# zmFPGA.net
KiCad netlist of a schematic drawn in EAGLE
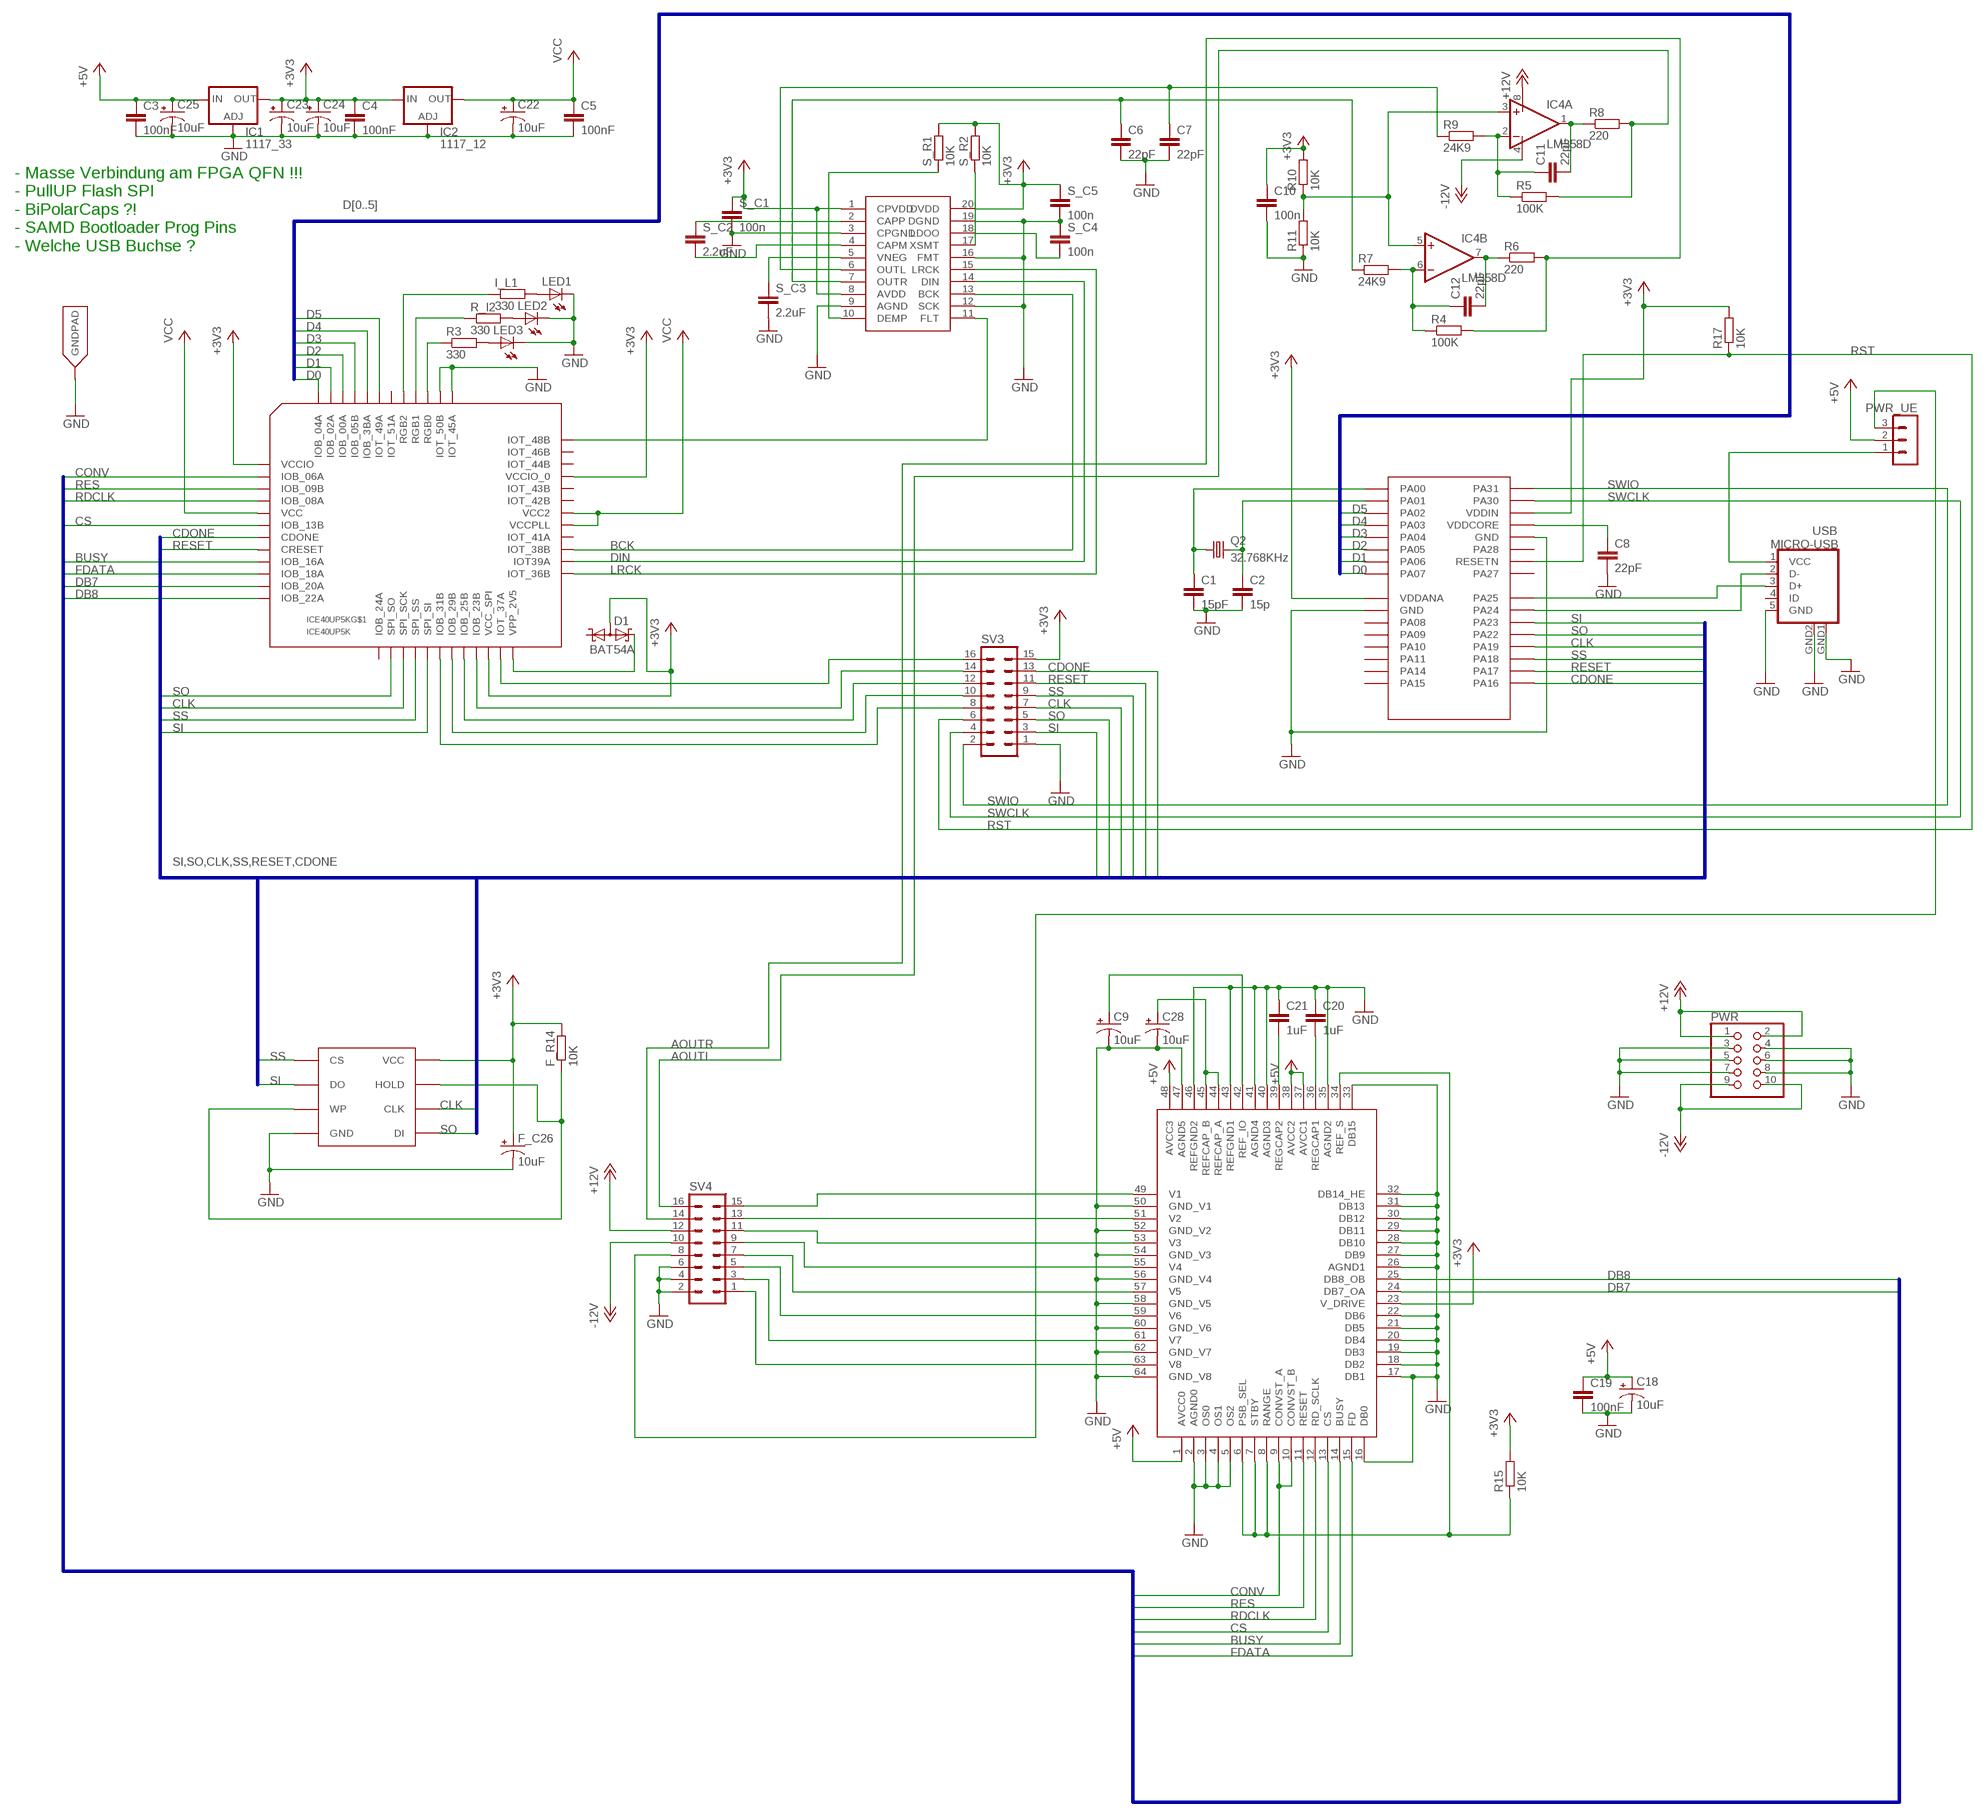
[diagram p0: schematic, sheet 1]

(export (version "E")
  (design (tool "Eeschema 10.0.6"))
  (components
    (comp (ref "AD7606")
      (value "AD7606")
      (footprint "eagle-import:LQFP64")
      (libsource (lib "eagle-import") (part "AD7606"))
    )
    (comp (ref "C1")
      (value "15pF")
      (footprint "eagle-import:C0805")
      (libsource (lib "eagle-import") (part "C-EUC0805"))
    )
    (comp (ref "C2")
      (value "15p")
      (footprint "eagle-import:C0805")
      (libsource (lib "eagle-import") (part "C-EUC0805"))
    )
    (comp (ref "C3")
      (value "100nF")
      (footprint "eagle-import:C0805")
      (libsource (lib "eagle-import") (part "C-EUC0805"))
    )
    (comp (ref "C4")
      (value "100nF")
      (footprint "eagle-import:C0805")
      (libsource (lib "eagle-import") (part "C-EUC0805"))
    )
    (comp (ref "C5")
      (value "100nF")
      (footprint "eagle-import:C0805")
      (libsource (lib "eagle-import") (part "C-EUC0805"))
    )
    (comp (ref "C6")
      (value "22pF")
      (footprint "eagle-import:C0805")
      (libsource (lib "eagle-import") (part "C-EUC0805"))
    )
    (comp (ref "C7")
      (value "22pF")
      (footprint "eagle-import:C0805")
      (libsource (lib "eagle-import") (part "C-EUC0805"))
    )
    (comp (ref "C8")
      (value "22pF")
      (footprint "eagle-import:C0805")
      (libsource (lib "eagle-import") (part "C-EUC0805"))
    )
    (comp (ref "C9")
      (value "10uF")
      (footprint "eagle-import:EIA3216")
      (libsource (lib "eagle-import") (part "10UF-POLAR-EIA3216-16V-10%(TANT)"))
    )
    (comp (ref "C10")
      (value "100n")
      (footprint "eagle-import:C0805")
      (libsource (lib "eagle-import") (part "C-EUC0805"))
    )
    (comp (ref "C11")
      (value "22pF")
      (footprint "eagle-import:C0805")
      (libsource (lib "eagle-import") (part "C-EUC0805"))
    )
    (comp (ref "C12")
      (value "22pF")
      (footprint "eagle-import:C0805")
      (libsource (lib "eagle-import") (part "C-EUC0805"))
    )
    (comp (ref "C18")
      (value "10uF")
      (footprint "eagle-import:EIA3216")
      (libsource (lib "eagle-import") (part "10UF-POLAR-EIA3216-16V-10%(TANT)"))
    )
    (comp (ref "C19")
      (value "100nF")
      (footprint "eagle-import:C0805")
      (libsource (lib "eagle-import") (part "C-EUC0805"))
    )
    (comp (ref "C20")
      (value "1uF")
      (footprint "eagle-import:C0805")
      (libsource (lib "eagle-import") (part "C-EUC0805"))
    )
    (comp (ref "C21")
      (value "1uF")
      (footprint "eagle-import:C0805")
      (libsource (lib "eagle-import") (part "C-EUC0805"))
    )
    (comp (ref "C22")
      (value "10uF")
      (footprint "eagle-import:EIA3216")
      (libsource (lib "eagle-import") (part "10UF-POLAR-EIA3216-16V-10%(TANT)"))
    )
    (comp (ref "C23")
      (value "10uF")
      (footprint "eagle-import:EIA3216")
      (libsource (lib "eagle-import") (part "10UF-POLAR-EIA3216-16V-10%(TANT)"))
    )
    (comp (ref "C24")
      (value "10uF")
      (footprint "eagle-import:EIA3216")
      (libsource (lib "eagle-import") (part "10UF-POLAR-EIA3216-16V-10%(TANT)"))
    )
    (comp (ref "C25")
      (value "10uF")
      (footprint "eagle-import:EIA3216")
      (libsource (lib "eagle-import") (part "10UF-POLAR-EIA3216-16V-10%(TANT)"))
    )
    (comp (ref "C28")
      (value "10uF")
      (footprint "eagle-import:EIA3216")
      (libsource (lib "eagle-import") (part "10UF-POLAR-EIA3216-16V-10%(TANT)"))
    )
    (comp (ref "D1")
      (value "BAT54A")
      (footprint "eagle-import:SOT23")
      (libsource (lib "eagle-import") (part "BAT54A"))
    )
    (comp (ref "F_C26")
      (value "10uF")
      (footprint "eagle-import:EIA3216")
      (libsource (lib "eagle-import") (part "10UF-POLAR-EIA3216-16V-10%(TANT)"))
    )
    (comp (ref "F_R14")
      (value "10K")
      (footprint "eagle-import:R0805")
      (libsource (lib "eagle-import") (part "R-EU_R0805"))
    )
    (comp (ref "IC1")
      (value "1117_33")
      (footprint "eagle-import:SOT223")
      (libsource (lib "eagle-import") (part "LD117A?S33TR"))
    )
    (comp (ref "IC2")
      (value "1117_12")
      (footprint "eagle-import:SOT223")
      (libsource (lib "eagle-import") (part "LD117A?S12TR"))
    )
    (comp (ref "IC4")
      (value "LM358D")
      (footprint "eagle-import:SO08")
      (libsource (lib "eagle-import") (part "LM358D"))
    )
    (comp (ref "ICE40UP5K")
      (value "ICE40UP5K")
      (footprint "eagle-import:QFN48")
      (libsource (lib "eagle-import") (part "ICE40UP5K_QFN48"))
    )
    (comp (ref "I_L1")
      (value "330")
      (footprint "eagle-import:R0805")
      (libsource (lib "eagle-import") (part "R-EU_R0805"))
    )
    (comp (ref "LED1")
      (value "LEDSMT1206")
      (footprint "eagle-import:1206")
      (libsource (lib "eagle-import") (part "LEDSMT1206"))
    )
    (comp (ref "LED2")
      (value "LEDSMT1206")
      (footprint "eagle-import:1206")
      (libsource (lib "eagle-import") (part "LEDSMT1206"))
    )
    (comp (ref "LED3")
      (value "LEDSMT1206")
      (footprint "eagle-import:1206")
      (libsource (lib "eagle-import") (part "LEDSMT1206"))
    )
    (comp (ref "PCM5102")
      (value "PCM5102")
      (footprint "eagle-import:TSSOP20")
      (libsource (lib "eagle-import") (part "PCM5102"))
    )
    (comp (ref "PWR")
      (value "PINHD-2X5")
      (footprint "eagle-import:2X05")
      (libsource (lib "eagle-import") (part "PINHD-2X5"))
    )
    (comp (ref "PWR_UE")
      (value "MA03-1")
      (footprint "eagle-import:MA03-1")
      (libsource (lib "eagle-import") (part "MA03-1"))
    )
    (comp (ref "Q2")
      (value "32.768KHz")
      (footprint "eagle-import:MM39SL")
      (libsource (lib "eagle-import") (part "CRYSTALMM39SL"))
    )
    (comp (ref "R3")
      (value "330")
      (footprint "eagle-import:R0805")
      (libsource (lib "eagle-import") (part "R-EU_R0805"))
    )
    (comp (ref "R4")
      (value "100K")
      (footprint "eagle-import:R0805")
      (libsource (lib "eagle-import") (part "R-EU_R0805"))
    )
    (comp (ref "R5")
      (value "100K")
      (footprint "eagle-import:R0805")
      (libsource (lib "eagle-import") (part "R-EU_R0805"))
    )
    (comp (ref "R6")
      (value "220")
      (footprint "eagle-import:R0805")
      (libsource (lib "eagle-import") (part "R-EU_R0805"))
    )
    (comp (ref "R7")
      (value "24K9")
      (footprint "eagle-import:R0805")
      (libsource (lib "eagle-import") (part "R-EU_R0805"))
    )
    (comp (ref "R8")
      (value "220")
      (footprint "eagle-import:R0805")
      (libsource (lib "eagle-import") (part "R-EU_R0805"))
    )
    (comp (ref "R9")
      (value "24K9")
      (footprint "eagle-import:R0805")
      (libsource (lib "eagle-import") (part "R-EU_R0805"))
    )
    (comp (ref "R10")
      (value "10K")
      (footprint "eagle-import:R0805")
      (libsource (lib "eagle-import") (part "R-EU_R0805"))
    )
    (comp (ref "R11")
      (value "10K")
      (footprint "eagle-import:R0805")
      (libsource (lib "eagle-import") (part "R-EU_R0805"))
    )
    (comp (ref "R15")
      (value "10K")
      (footprint "eagle-import:R0805")
      (libsource (lib "eagle-import") (part "R-EU_R0805"))
    )
    (comp (ref "R17")
      (value "10K")
      (footprint "eagle-import:R1206")
      (libsource (lib "eagle-import") (part "R-EU_R1206"))
    )
    (comp (ref "R_I2")
      (value "330")
      (footprint "eagle-import:R0805")
      (libsource (lib "eagle-import") (part "R-EU_R0805"))
    )
    (comp (ref "SV3")
      (value "MA08-2")
      (footprint "eagle-import:MA08-2")
      (libsource (lib "eagle-import") (part "MA08-2"))
    )
    (comp (ref "SV4")
      (value "MA08-2")
      (footprint "eagle-import:MA08-2")
      (libsource (lib "eagle-import") (part "MA08-2"))
    )
    (comp (ref "S_C1")
      (value "100n")
      (footprint "eagle-import:C0805")
      (libsource (lib "eagle-import") (part "C-EUC0805"))
    )
    (comp (ref "S_C2")
      (value "2.2uF")
      (footprint "eagle-import:C0805")
      (libsource (lib "eagle-import") (part "C-EUC0805"))
    )
    (comp (ref "S_C3")
      (value "2.2uF")
      (footprint "eagle-import:C0805")
      (libsource (lib "eagle-import") (part "C-EUC0805"))
    )
    (comp (ref "S_C4")
      (value "100n")
      (footprint "eagle-import:C0805")
      (libsource (lib "eagle-import") (part "C-EUC0805"))
    )
    (comp (ref "S_C5")
      (value "100n")
      (footprint "eagle-import:C0805")
      (libsource (lib "eagle-import") (part "C-EUC0805"))
    )
    (comp (ref "S_R1")
      (value "10K")
      (footprint "eagle-import:R0805")
      (libsource (lib "eagle-import") (part "R-EU_R0805"))
    )
    (comp (ref "S_R2")
      (value "10K")
      (footprint "eagle-import:R0805")
      (libsource (lib "eagle-import") (part "R-EU_R0805"))
    )
    (comp (ref "U$1")
      (value "W25Q32")
      (footprint "eagle-import:SOP-8")
      (libsource (lib "eagle-import") (part "W25Q32"))
    )
    (comp (ref "U$2")
      (value "SAMD21_TQFP32")
      (footprint "eagle-import:32-TQFP")
      (libsource (lib "eagle-import") (part "SAMD21_TQFP32"))
    )
    (comp (ref "USB")
      (value "MICRO-USB")
      (footprint "eagle-import:MICRO-USB")
      (libsource (lib "eagle-import") (part "MICRO-USB"))
    )
  )
  (nets
    (net (code "1") (name "+3V3") (class "Default")
      (node (ref "AD7606") (pin "23") (pinfunction "V_DRIVE_23") (pintype "bidirectional"))
      (node (ref "C10") (pin "1") (pinfunction "1_1") (pintype "passive"))
      (node (ref "C23") (pin "+") (pinfunction "+_+") (pintype "passive"))
      (node (ref "C24") (pin "+") (pinfunction "+_+") (pintype "passive"))
      (node (ref "C4") (pin "1") (pinfunction "1_1") (pintype "passive"))
      (node (ref "D1") (pin "3") (pinfunction "AA_3") (pintype "passive"))
      (node (ref "F_C26") (pin "+") (pinfunction "+_+") (pintype "passive"))
      (node (ref "F_R14") (pin "2") (pinfunction "2_2") (pintype "passive"))
      (node (ref "IC1") (pin "4") (pinfunction "OUT_4") (pintype "passive"))
      (node (ref "IC2") (pin "3") (pinfunction "IN_3") (pintype "input"))
      (node (ref "ICE40UP5K") (pin "1") (pinfunction "VCCIO_1") (pintype "power_in"))
      (node (ref "ICE40UP5K") (pin "22") (pinfunction "VCC_SPI_22") (pintype "bidirectional"))
      (node (ref "ICE40UP5K") (pin "33") (pinfunction "VCCIO_0_33") (pintype "power_in"))
      (node (ref "PCM5102") (pin "1") (pinfunction "CPVDD_1") (pintype "bidirectional"))
      (node (ref "PCM5102") (pin "20") (pinfunction "DVDD_20") (pintype "bidirectional"))
      (node (ref "PCM5102") (pin "8") (pinfunction "AVDD_8") (pintype "bidirectional"))
      (node (ref "R10") (pin "2") (pinfunction "2_2") (pintype "passive"))
      (node (ref "R15") (pin "2") (pinfunction "2_2") (pintype "passive"))
      (node (ref "R17") (pin "2") (pinfunction "2_2") (pintype "passive"))
      (node (ref "SV3") (pin "15") (pinfunction "15_15") (pintype "passive"))
      (node (ref "S_C1") (pin "1") (pinfunction "1_1") (pintype "passive"))
      (node (ref "S_C5") (pin "1") (pinfunction "1_1") (pintype "passive"))
      (node (ref "S_R1") (pin "2") (pinfunction "2_2") (pintype "passive"))
      (node (ref "S_R2") (pin "2") (pinfunction "2_2") (pintype "passive"))
      (node (ref "U$1") (pin "8") (pinfunction "VCC_8") (pintype "power_in"))
      (node (ref "U$2") (pin "30") (pinfunction "VDDIN_30") (pintype "bidirectional"))
      (node (ref "U$2") (pin "9") (pinfunction "VDDANA_9") (pintype "bidirectional"))
    )
    (net (code "2") (name "+5V") (class "Default")
      (node (ref "AD7606") (pin "1") (pinfunction "AVCC0_1") (pintype "bidirectional"))
      (node (ref "AD7606") (pin "37") (pinfunction "AVCC1_37") (pintype "bidirectional"))
      (node (ref "AD7606") (pin "38") (pinfunction "AVCC2_38") (pintype "bidirectional"))
      (node (ref "AD7606") (pin "48") (pinfunction "AVCC3_48") (pintype "bidirectional"))
      (node (ref "C18") (pin "+") (pinfunction "+_+") (pintype "passive"))
      (node (ref "C19") (pin "1") (pinfunction "1_1") (pintype "passive"))
      (node (ref "C25") (pin "+") (pinfunction "+_+") (pintype "passive"))
      (node (ref "C3") (pin "1") (pinfunction "1_1") (pintype "passive"))
      (node (ref "IC1") (pin "3") (pinfunction "IN_3") (pintype "input"))
      (node (ref "PWR_UE") (pin "2") (pinfunction "2_2") (pintype "passive"))
    )
    (net (code "3") (name "+12V") (class "Default")
      (node (ref "IC4") (pin "8") (pinfunction "V+_8") (pintype "power_in"))
      (node (ref "PWR") (pin "1") (pinfunction "1_1") (pintype "passive"))
      (node (ref "PWR") (pin "2") (pinfunction "2_2") (pintype "passive"))
      (node (ref "SV4") (pin "12") (pinfunction "12_12") (pintype "passive"))
    )
    (net (code "4") (name "-12V") (class "Default")
      (node (ref "IC4") (pin "4") (pinfunction "V-_4") (pintype "power_in"))
      (node (ref "PWR") (pin "10") (pinfunction "10_10") (pintype "passive"))
      (node (ref "PWR") (pin "9") (pinfunction "9_9") (pintype "passive"))
      (node (ref "SV4") (pin "10") (pinfunction "10_10") (pintype "passive"))
    )
    (net (code "5") (name "/AOUTL") (class "Default")
      (node (ref "R5") (pin "2") (pinfunction "2_2") (pintype "passive"))
      (node (ref "R8") (pin "2") (pinfunction "2_2") (pintype "passive"))
      (node (ref "SV4") (pin "16") (pinfunction "16_16") (pintype "passive"))
    )
    (net (code "6") (name "/AOUTR") (class "Default")
      (node (ref "R4") (pin "2") (pinfunction "2_2") (pintype "passive"))
      (node (ref "R6") (pin "2") (pinfunction "2_2") (pintype "passive"))
      (node (ref "SV4") (pin "14") (pinfunction "14_14") (pintype "passive"))
    )
    (net (code "7") (name "/BCK") (class "Default")
      (node (ref "ICE40UP5K") (pin "27") (pinfunction "IOT_38B_27") (pintype "bidirectional"))
      (node (ref "PCM5102") (pin "13") (pinfunction "BCK_13") (pintype "bidirectional"))
    )
    (net (code "8") (name "/BUSY") (class "Default")
      (node (ref "AD7606") (pin "14") (pinfunction "BUSY_14") (pintype "bidirectional"))
      (node (ref "ICE40UP5K") (pin "9") (pinfunction "IOB_16A_9") (pintype "bidirectional"))
    )
    (net (code "9") (name "/CDONE") (class "Default")
      (node (ref "ICE40UP5K") (pin "7") (pinfunction "CDONE_7") (pintype "bidirectional"))
      (node (ref "SV3") (pin "13") (pinfunction "13_13") (pintype "passive"))
      (node (ref "U$2") (pin "17") (pinfunction "PA16_17") (pintype "bidirectional"))
    )
    (net (code "10") (name "/CLK") (class "Default")
      (node (ref "ICE40UP5K") (pin "15") (pinfunction "SPI_SCK_15") (pintype "bidirectional"))
      (node (ref "SV3") (pin "7") (pinfunction "7_7") (pintype "passive"))
      (node (ref "U$1") (pin "6") (pinfunction "CLK_6") (pintype "bidirectional"))
      (node (ref "U$2") (pin "20") (pinfunction "PA19_20") (pintype "bidirectional"))
    )
    (net (code "11") (name "/CONV") (class "Default")
      (node (ref "AD7606") (pin "10") (pinfunction "CONVST_B_10") (pintype "bidirectional"))
      (node (ref "AD7606") (pin "9") (pinfunction "CONVST_A_9") (pintype "bidirectional"))
      (node (ref "ICE40UP5K") (pin "2") (pinfunction "IOB_06A_2") (pintype "bidirectional"))
    )
    (net (code "12") (name "/CS") (class "Default")
      (node (ref "AD7606") (pin "13") (pinfunction "CS_13") (pintype "bidirectional"))
      (node (ref "ICE40UP5K") (pin "6") (pinfunction "IOB_13B_6") (pintype "bidirectional"))
    )
    (net (code "13") (name "/D0") (class "Default")
      (node (ref "ICE40UP5K") (pin "48") (pinfunction "IOB_04A_48") (pintype "bidirectional"))
      (node (ref "U$2") (pin "8") (pinfunction "PA07_8") (pintype "bidirectional"))
    )
    (net (code "14") (name "/D1") (class "Default")
      (node (ref "ICE40UP5K") (pin "47") (pinfunction "IOB_02A_47") (pintype "bidirectional"))
      (node (ref "U$2") (pin "7") (pinfunction "PA06_7") (pintype "bidirectional"))
    )
    (net (code "15") (name "/D2") (class "Default")
      (node (ref "ICE40UP5K") (pin "46") (pinfunction "IOB_00A_46") (pintype "bidirectional"))
      (node (ref "U$2") (pin "6") (pinfunction "PA05_6") (pintype "bidirectional"))
    )
    (net (code "16") (name "/D3") (class "Default")
      (node (ref "ICE40UP5K") (pin "45") (pinfunction "IOB_05B_45") (pintype "bidirectional"))
      (node (ref "U$2") (pin "5") (pinfunction "PA04_5") (pintype "bidirectional"))
    )
    (net (code "17") (name "/D4") (class "Default")
      (node (ref "ICE40UP5K") (pin "44") (pinfunction "IOB_3BA_44") (pintype "bidirectional"))
      (node (ref "U$2") (pin "4") (pinfunction "PA03_4") (pintype "bidirectional"))
    )
    (net (code "18") (name "/D5") (class "Default")
      (node (ref "ICE40UP5K") (pin "43") (pinfunction "IOT_49A_43") (pintype "bidirectional"))
      (node (ref "U$2") (pin "3") (pinfunction "PA02_3") (pintype "bidirectional"))
    )
    (net (code "19") (name "/DB7") (class "Default")
      (node (ref "AD7606") (pin "24") (pinfunction "DB7_OA_24") (pintype "bidirectional"))
      (node (ref "ICE40UP5K") (pin "11") (pinfunction "IOB_20A_11") (pintype "bidirectional"))
    )
    (net (code "20") (name "/DB8") (class "Default")
      (node (ref "AD7606") (pin "25") (pinfunction "DB8_OB_25") (pintype "bidirectional"))
      (node (ref "ICE40UP5K") (pin "12") (pinfunction "IOB_22A_12") (pintype "bidirectional"))
    )
    (net (code "21") (name "/DIN") (class "Default")
      (node (ref "ICE40UP5K") (pin "26") (pinfunction "IOT39A_26") (pintype "bidirectional"))
      (node (ref "PCM5102") (pin "14") (pinfunction "DIN_14") (pintype "bidirectional"))
    )
    (net (code "23") (name "/FDATA") (class "Default")
      (node (ref "AD7606") (pin "15") (pinfunction "FD_15") (pintype "bidirectional"))
      (node (ref "ICE40UP5K") (pin "10") (pinfunction "IOB_18A_10") (pintype "bidirectional"))
    )
    (net (code "24") (name "/LRCK") (class "Default")
      (node (ref "ICE40UP5K") (pin "25") (pinfunction "IOT_36B_25") (pintype "bidirectional"))
      (node (ref "PCM5102") (pin "15") (pinfunction "LRCK_15") (pintype "bidirectional"))
    )
    (net (code "25") (name "/RDCLK") (class "Default")
      (node (ref "AD7606") (pin "12") (pinfunction "RD_SCLK_12") (pintype "bidirectional"))
      (node (ref "ICE40UP5K") (pin "4") (pinfunction "IOB_08A_4") (pintype "bidirectional"))
    )
    (net (code "26") (name "/RES") (class "Default")
      (node (ref "AD7606") (pin "11") (pinfunction "RESET_11") (pintype "bidirectional"))
      (node (ref "ICE40UP5K") (pin "3") (pinfunction "IOB_09B_3") (pintype "bidirectional"))
    )
    (net (code "27") (name "/RESET") (class "Default")
      (node (ref "ICE40UP5K") (pin "8") (pinfunction "CRESET_8") (pintype "bidirectional"))
      (node (ref "SV3") (pin "11") (pinfunction "11_11") (pintype "passive"))
      (node (ref "U$2") (pin "18") (pinfunction "PA17_18") (pintype "bidirectional"))
    )
    (net (code "28") (name "/RST") (class "Default")
      (node (ref "R17") (pin "1") (pinfunction "1_1") (pintype "passive"))
      (node (ref "SV3") (pin "6") (pinfunction "6_6") (pintype "passive"))
      (node (ref "U$2") (pin "26") (pinfunction "RESETN_26") (pintype "bidirectional"))
    )
    (net (code "29") (name "/SI") (class "Default")
      (node (ref "ICE40UP5K") (pin "17") (pinfunction "SPI_SI_17") (pintype "bidirectional"))
      (node (ref "SV3") (pin "3") (pinfunction "3_3") (pintype "passive"))
      (node (ref "U$1") (pin "2") (pinfunction "DO_2") (pintype "bidirectional"))
      (node (ref "U$2") (pin "22") (pinfunction "PA23_22") (pintype "bidirectional"))
    )
    (net (code "30") (name "/SO") (class "Default")
      (node (ref "ICE40UP5K") (pin "14") (pinfunction "SPI_SO_14") (pintype "bidirectional"))
      (node (ref "SV3") (pin "5") (pinfunction "5_5") (pintype "passive"))
      (node (ref "U$1") (pin "5") (pinfunction "DI_5") (pintype "bidirectional"))
      (node (ref "U$2") (pin "21") (pinfunction "PA22_21") (pintype "bidirectional"))
    )
    (net (code "31") (name "/SS") (class "Default")
      (node (ref "ICE40UP5K") (pin "16") (pinfunction "SPI_SS_16") (pintype "bidirectional"))
      (node (ref "SV3") (pin "9") (pinfunction "9_9") (pintype "passive"))
      (node (ref "U$1") (pin "1") (pinfunction "CS_1") (pintype "bidirectional"))
      (node (ref "U$2") (pin "19") (pinfunction "PA18_19") (pintype "bidirectional"))
    )
    (net (code "32") (name "/SWCLK") (class "Default")
      (node (ref "SV3") (pin "4") (pinfunction "4_4") (pintype "passive"))
      (node (ref "U$2") (pin "31") (pinfunction "PA30_31") (pintype "bidirectional"))
    )
    (net (code "33") (name "/SWIO") (class "Default")
      (node (ref "SV3") (pin "2") (pinfunction "2_2") (pintype "passive"))
      (node (ref "U$2") (pin "32") (pinfunction "PA31_32") (pintype "bidirectional"))
    )
    (net (code "35") (name "GND") (class "Default")
      (node (ref "AD7606") (pin "16") (pinfunction "DB0_16") (pintype "bidirectional"))
      (node (ref "AD7606") (pin "17") (pinfunction "DB1_17") (pintype "bidirectional"))
      (node (ref "AD7606") (pin "18") (pinfunction "DB2_18") (pintype "bidirectional"))
      (node (ref "AD7606") (pin "19") (pinfunction "DB3_19") (pintype "bidirectional"))
      (node (ref "AD7606") (pin "2") (pinfunction "AGND0_2") (pintype "bidirectional"))
      (node (ref "AD7606") (pin "20") (pinfunction "DB4_20") (pintype "bidirectional"))
      (node (ref "AD7606") (pin "21") (pinfunction "DB5_21") (pintype "bidirectional"))
      (node (ref "AD7606") (pin "22") (pinfunction "DB6_22") (pintype "bidirectional"))
      (node (ref "AD7606") (pin "26") (pinfunction "AGND1_26") (pintype "bidirectional"))
      (node (ref "AD7606") (pin "27") (pinfunction "DB9_27") (pintype "bidirectional"))
      (node (ref "AD7606") (pin "28") (pinfunction "DB10_28") (pintype "bidirectional"))
      (node (ref "AD7606") (pin "29") (pinfunction "DB11_29") (pintype "bidirectional"))
      (node (ref "AD7606") (pin "3") (pinfunction "OS0_3") (pintype "bidirectional"))
      (node (ref "AD7606") (pin "30") (pinfunction "DB12_30") (pintype "bidirectional"))
      (node (ref "AD7606") (pin "31") (pinfunction "DB13_31") (pintype "bidirectional"))
      (node (ref "AD7606") (pin "32") (pinfunction "DB14_HE_32") (pintype "bidirectional"))
      (node (ref "AD7606") (pin "33") (pinfunction "DB15_33") (pintype "bidirectional"))
      (node (ref "AD7606") (pin "35") (pinfunction "AGND2_35") (pintype "bidirectional"))
      (node (ref "AD7606") (pin "4") (pinfunction "OS1_4") (pintype "bidirectional"))
      (node (ref "AD7606") (pin "40") (pinfunction "AGND3_40") (pintype "bidirectional"))
      (node (ref "AD7606") (pin "41") (pinfunction "AGND4_41") (pintype "bidirectional"))
      (node (ref "AD7606") (pin "43") (pinfunction "REFGND1_43") (pintype "bidirectional"))
      (node (ref "AD7606") (pin "46") (pinfunction "REFGND2_46") (pintype "bidirectional"))
      (node (ref "AD7606") (pin "47") (pinfunction "AGND5_47") (pintype "bidirectional"))
      (node (ref "AD7606") (pin "5") (pinfunction "OS2_5") (pintype "bidirectional"))
      (node (ref "AD7606") (pin "50") (pinfunction "GND_V1_50") (pintype "bidirectional"))
      (node (ref "AD7606") (pin "52") (pinfunction "GND_V2_52") (pintype "bidirectional"))
      (node (ref "AD7606") (pin "54") (pinfunction "GND_V3_54") (pintype "bidirectional"))
      (node (ref "AD7606") (pin "56") (pinfunction "GND_V4_56") (pintype "bidirectional"))
      (node (ref "AD7606") (pin "58") (pinfunction "GND_V5_58") (pintype "bidirectional"))
      (node (ref "AD7606") (pin "60") (pinfunction "GND_V6_60") (pintype "bidirectional"))
      (node (ref "AD7606") (pin "62") (pinfunction "GND_V7_62") (pintype "bidirectional"))
      (node (ref "AD7606") (pin "64") (pinfunction "GND_V8_64") (pintype "bidirectional"))
      (node (ref "C1") (pin "2") (pinfunction "2_2") (pintype "passive"))
      (node (ref "C10") (pin "2") (pinfunction "2_2") (pintype "passive"))
      (node (ref "C18") (pin "-") (pinfunction "-_-") (pintype "passive"))
      (node (ref "C19") (pin "2") (pinfunction "2_2") (pintype "passive"))
      (node (ref "C2") (pin "2") (pinfunction "2_2") (pintype "passive"))
      (node (ref "C20") (pin "1") (pinfunction "1_1") (pintype "passive"))
      (node (ref "C21") (pin "1") (pinfunction "1_1") (pintype "passive"))
      (node (ref "C22") (pin "-") (pinfunction "-_-") (pintype "passive"))
      (node (ref "C23") (pin "-") (pinfunction "-_-") (pintype "passive"))
      (node (ref "C24") (pin "-") (pinfunction "-_-") (pintype "passive"))
      (node (ref "C25") (pin "-") (pinfunction "-_-") (pintype "passive"))
      (node (ref "C28") (pin "-") (pinfunction "-_-") (pintype "passive"))
      (node (ref "C3") (pin "2") (pinfunction "2_2") (pintype "passive"))
      (node (ref "C4") (pin "2") (pinfunction "2_2") (pintype "passive"))
      (node (ref "C5") (pin "2") (pinfunction "2_2") (pintype "passive"))
      (node (ref "C6") (pin "2") (pinfunction "2_2") (pintype "passive"))
      (node (ref "C7") (pin "2") (pinfunction "2_2") (pintype "passive"))
      (node (ref "C8") (pin "2") (pinfunction "2_2") (pintype "passive"))
      (node (ref "C9") (pin "-") (pinfunction "-_-") (pintype "passive"))
      (node (ref "F_C26") (pin "-") (pinfunction "-_-") (pintype "passive"))
      (node (ref "IC1") (pin "1") (pinfunction "ADJ_1") (pintype "input"))
      (node (ref "IC2") (pin "1") (pinfunction "ADJ_1") (pintype "input"))
      (node (ref "ICE40UP5K") (pin "37") (pinfunction "IOT_45A_37") (pintype "bidirectional"))
      (node (ref "ICE40UP5K") (pin "38") (pinfunction "IOT_50B_38") (pintype "bidirectional"))
      (node (ref "ICE40UP5K") (pin "EXP") (pinfunction "GNDPAD_EXP") (pintype "power_in"))
      (node (ref "LED1") (pin "C") (pinfunction "C_C") (pintype "passive"))
      (node (ref "LED2") (pin "C") (pinfunction "C_C") (pintype "passive"))
      (node (ref "LED3") (pin "C") (pinfunction "C_C") (pintype "passive"))
      (node (ref "PCM5102") (pin "12") (pinfunction "SCK_12") (pintype "bidirectional"))
      (node (ref "PCM5102") (pin "16") (pinfunction "FMT_16") (pintype "bidirectional"))
      (node (ref "PCM5102") (pin "19") (pinfunction "DGND_19") (pintype "bidirectional"))
      (node (ref "PCM5102") (pin "3") (pinfunction "CPGND_3") (pintype "bidirectional"))
      (node (ref "PCM5102") (pin "9") (pinfunction "AGND_9") (pintype "bidirectional"))
      (node (ref "PWR") (pin "3") (pinfunction "3_3") (pintype "passive"))
      (node (ref "PWR") (pin "4") (pinfunction "4_4") (pintype "passive"))
      (node (ref "PWR") (pin "5") (pinfunction "5_5") (pintype "passive"))
      (node (ref "PWR") (pin "6") (pinfunction "6_6") (pintype "passive"))
      (node (ref "PWR") (pin "7") (pinfunction "7_7") (pintype "passive"))
      (node (ref "PWR") (pin "8") (pinfunction "8_8") (pintype "passive"))
      (node (ref "R11") (pin "1") (pinfunction "1_1") (pintype "passive"))
      (node (ref "SV3") (pin "1") (pinfunction "1_1") (pintype "passive"))
      (node (ref "SV4") (pin "2") (pinfunction "2_2") (pintype "passive"))
      (node (ref "SV4") (pin "4") (pinfunction "4_4") (pintype "passive"))
      (node (ref "SV4") (pin "6") (pinfunction "6_6") (pintype "passive"))
      (node (ref "S_C1") (pin "2") (pinfunction "2_2") (pintype "passive"))
      (node (ref "S_C3") (pin "2") (pinfunction "2_2") (pintype "passive"))
      (node (ref "S_C4") (pin "1") (pinfunction "1_1") (pintype "passive"))
      (node (ref "S_C5") (pin "2") (pinfunction "2_2") (pintype "passive"))
      (node (ref "U$1") (pin "4") (pinfunction "GND_4") (pintype "power_in"))
      (node (ref "U$2") (pin "10") (pinfunction "GND_10") (pintype "bidirectional"))
      (node (ref "U$2") (pin "28") (pinfunction "GND_28") (pintype "bidirectional"))
      (node (ref "USB") (pin "5") (pinfunction "GND_5") (pintype "power_in"))
      (node (ref "USB") (pin "GND1") (pinfunction "GND_GND1") (pintype "power_in"))
      (node (ref "USB") (pin "GND2") (pinfunction "GND_GND2") (pintype "power_in"))
    )
    (net (code "36") (name "Net-(AD7606-PSB_SEL)") (class "Default")
      (node (ref "AD7606") (pin "34") (pinfunction "REF_S_34") (pintype "bidirectional"))
      (node (ref "AD7606") (pin "6") (pinfunction "PSB_SEL_6") (pintype "bidirectional"))
      (node (ref "AD7606") (pin "7") (pinfunction "STBY_7") (pintype "bidirectional"))
      (node (ref "AD7606") (pin "8") (pinfunction "RANGE_8") (pintype "bidirectional"))
      (node (ref "R15") (pin "1") (pinfunction "1_1") (pintype "passive"))
    )
    (net (code "37") (name "Net-(AD7606-REFCAP_A)") (class "Default")
      (node (ref "AD7606") (pin "44") (pinfunction "REFCAP_A_44") (pintype "bidirectional"))
      (node (ref "AD7606") (pin "45") (pinfunction "REFCAP_B_45") (pintype "bidirectional"))
      (node (ref "C28") (pin "+") (pinfunction "+_+") (pintype "passive"))
    )
    (net (code "38") (name "Net-(AD7606-REF_IO)") (class "Default")
      (node (ref "AD7606") (pin "42") (pinfunction "REF_IO_42") (pintype "bidirectional"))
      (node (ref "C9") (pin "+") (pinfunction "+_+") (pintype "passive"))
    )
    (net (code "39") (name "Net-(AD7606-REGCAP1)") (class "Default")
      (node (ref "AD7606") (pin "36") (pinfunction "REGCAP1_36") (pintype "bidirectional"))
      (node (ref "C20") (pin "2") (pinfunction "2_2") (pintype "passive"))
    )
    (net (code "40") (name "Net-(AD7606-REGCAP2)") (class "Default")
      (node (ref "AD7606") (pin "39") (pinfunction "REGCAP2_39") (pintype "bidirectional"))
      (node (ref "C21") (pin "2") (pinfunction "2_2") (pintype "passive"))
    )
    (net (code "41") (name "Net-(AD7606-V1)") (class "Default")
      (node (ref "AD7606") (pin "49") (pinfunction "V1_49") (pintype "bidirectional"))
      (node (ref "SV4") (pin "15") (pinfunction "15_15") (pintype "passive"))
    )
    (net (code "42") (name "Net-(AD7606-V2)") (class "Default")
      (node (ref "AD7606") (pin "51") (pinfunction "V2_51") (pintype "bidirectional"))
      (node (ref "SV4") (pin "13") (pinfunction "13_13") (pintype "passive"))
    )
    (net (code "43") (name "Net-(AD7606-V3)") (class "Default")
      (node (ref "AD7606") (pin "53") (pinfunction "V3_53") (pintype "bidirectional"))
      (node (ref "SV4") (pin "11") (pinfunction "11_11") (pintype "passive"))
    )
    (net (code "44") (name "Net-(AD7606-V4)") (class "Default")
      (node (ref "AD7606") (pin "55") (pinfunction "V4_55") (pintype "bidirectional"))
      (node (ref "SV4") (pin "9") (pinfunction "9_9") (pintype "passive"))
    )
    (net (code "45") (name "Net-(AD7606-V5)") (class "Default")
      (node (ref "AD7606") (pin "57") (pinfunction "V5_57") (pintype "bidirectional"))
      (node (ref "SV4") (pin "7") (pinfunction "7_7") (pintype "passive"))
    )
    (net (code "46") (name "Net-(AD7606-V6)") (class "Default")
      (node (ref "AD7606") (pin "59") (pinfunction "V6_59") (pintype "bidirectional"))
      (node (ref "SV4") (pin "5") (pinfunction "5_5") (pintype "passive"))
    )
    (net (code "47") (name "Net-(AD7606-V7)") (class "Default")
      (node (ref "AD7606") (pin "61") (pinfunction "V7_61") (pintype "bidirectional"))
      (node (ref "SV4") (pin "3") (pinfunction "3_3") (pintype "passive"))
    )
    (net (code "48") (name "Net-(AD7606-V8)") (class "Default")
      (node (ref "AD7606") (pin "63") (pinfunction "V8_63") (pintype "bidirectional"))
      (node (ref "SV4") (pin "1") (pinfunction "1_1") (pintype "passive"))
    )
    (net (code "49") (name "Net-(D1-K2)") (class "Default")
      (node (ref "D1") (pin "2") (pinfunction "K2_2") (pintype "passive"))
      (node (ref "ICE40UP5K") (pin "24") (pinfunction "VPP_2V5_24") (pintype "power_in"))
    )
    (net (code "50") (name "Net-(IC4A-+IN)") (class "Default")
      (node (ref "IC4") (pin "3") (pinfunction "+IN_3") (pintype "input"))
      (node (ref "IC4") (pin "5") (pinfunction "+IN_5") (pintype "input"))
      (node (ref "R10") (pin "1") (pinfunction "1_1") (pintype "passive"))
      (node (ref "R11") (pin "2") (pinfunction "2_2") (pintype "passive"))
    )
    (net (code "51") (name "Net-(IC4A--IN)") (class "Default")
      (node (ref "C11") (pin "1") (pinfunction "1_1") (pintype "passive"))
      (node (ref "IC4") (pin "2") (pinfunction "-IN_2") (pintype "input"))
      (node (ref "R5") (pin "1") (pinfunction "1_1") (pintype "passive"))
      (node (ref "R9") (pin "2") (pinfunction "2_2") (pintype "passive"))
    )
    (net (code "52") (name "Net-(IC4A-OUT)") (class "Default")
      (node (ref "C11") (pin "2") (pinfunction "2_2") (pintype "passive"))
      (node (ref "IC4") (pin "1") (pinfunction "OUT_1") (pintype "output"))
      (node (ref "R8") (pin "1") (pinfunction "1_1") (pintype "passive"))
    )
    (net (code "53") (name "Net-(IC4B--IN)") (class "Default")
      (node (ref "C12") (pin "1") (pinfunction "1_1") (pintype "passive"))
      (node (ref "IC4") (pin "6") (pinfunction "-IN_6") (pintype "input"))
      (node (ref "R4") (pin "1") (pinfunction "1_1") (pintype "passive"))
      (node (ref "R7") (pin "2") (pinfunction "2_2") (pintype "passive"))
    )
    (net (code "54") (name "Net-(IC4B-OUT)") (class "Default")
      (node (ref "C12") (pin "2") (pinfunction "2_2") (pintype "passive"))
      (node (ref "IC4") (pin "7") (pinfunction "OUT_7") (pintype "output"))
      (node (ref "R6") (pin "1") (pinfunction "1_1") (pintype "passive"))
    )
    (net (code "55") (name "Net-(ICE40UP5KA-IOB_23B)") (class "Default")
      (node (ref "ICE40UP5K") (pin "21") (pinfunction "IOB_23B_21") (pintype "bidirectional"))
      (node (ref "SV3") (pin "14") (pinfunction "14_14") (pintype "passive"))
    )
    (net (code "56") (name "Net-(ICE40UP5KA-IOB_25B)") (class "Default")
      (node (ref "ICE40UP5K") (pin "20") (pinfunction "IOB_25B_20") (pintype "bidirectional"))
      (node (ref "SV3") (pin "12") (pinfunction "12_12") (pintype "passive"))
    )
    (net (code "57") (name "Net-(ICE40UP5KA-IOB_29B)") (class "Default")
      (node (ref "ICE40UP5K") (pin "19") (pinfunction "IOB_29B_19") (pintype "bidirectional"))
      (node (ref "SV3") (pin "10") (pinfunction "10_10") (pintype "passive"))
    )
    (net (code "58") (name "Net-(ICE40UP5KA-IOB_31B)") (class "Default")
      (node (ref "ICE40UP5K") (pin "18") (pinfunction "IOB_31B_18") (pintype "bidirectional"))
      (node (ref "SV3") (pin "8") (pinfunction "8_8") (pintype "passive"))
    )
    (net (code "59") (name "Net-(ICE40UP5KA-IOT_37A)") (class "Default")
      (node (ref "ICE40UP5K") (pin "23") (pinfunction "IOT_37A_23") (pintype "bidirectional"))
      (node (ref "SV3") (pin "16") (pinfunction "16_16") (pintype "passive"))
    )
    (net (code "60") (name "Net-(ICE40UP5KA-IOT_48B)") (class "Default")
      (node (ref "ICE40UP5K") (pin "36") (pinfunction "IOT_48B_36") (pintype "bidirectional"))
      (node (ref "PCM5102") (pin "11") (pinfunction "FLT_11") (pintype "bidirectional"))
    )
    (net (code "61") (name "Net-(ICE40UP5KA-RGB0)") (class "Default")
      (node (ref "ICE40UP5K") (pin "39") (pinfunction "RGB0_39") (pintype "bidirectional"))
      (node (ref "R3") (pin "1") (pinfunction "1_1") (pintype "passive"))
    )
    (net (code "62") (name "Net-(ICE40UP5KA-RGB1)") (class "Default")
      (node (ref "ICE40UP5K") (pin "40") (pinfunction "RGB1_40") (pintype "bidirectional"))
      (node (ref "R_I2") (pin "1") (pinfunction "1_1") (pintype "passive"))
    )
    (net (code "63") (name "Net-(ICE40UP5KA-RGB2)") (class "Default")
      (node (ref "ICE40UP5K") (pin "41") (pinfunction "RGB2_41") (pintype "bidirectional"))
      (node (ref "I_L1") (pin "1") (pinfunction "1_1") (pintype "passive"))
    )
    (net (code "64") (name "Net-(I_L1-Pad2)") (class "Default")
      (node (ref "I_L1") (pin "2") (pinfunction "2_2") (pintype "passive"))
      (node (ref "LED1") (pin "A") (pinfunction "A_A") (pintype "passive"))
    )
    (net (code "65") (name "Net-(LED2-PadA)") (class "Default")
      (node (ref "LED2") (pin "A") (pinfunction "A_A") (pintype "passive"))
      (node (ref "R_I2") (pin "2") (pinfunction "2_2") (pintype "passive"))
    )
    (net (code "66") (name "Net-(LED3-PadA)") (class "Default")
      (node (ref "LED3") (pin "A") (pinfunction "A_A") (pintype "passive"))
      (node (ref "R3") (pin "2") (pinfunction "2_2") (pintype "passive"))
    )
    (net (code "67") (name "Net-(PCM5102-CAPM)") (class "Default")
      (node (ref "PCM5102") (pin "4") (pinfunction "CAPM_4") (pintype "bidirectional"))
      (node (ref "S_C2") (pin "2") (pinfunction "2_2") (pintype "passive"))
    )
    (net (code "68") (name "Net-(PCM5102-CAPP)") (class "Default")
      (node (ref "PCM5102") (pin "2") (pinfunction "CAPP_2") (pintype "bidirectional"))
      (node (ref "S_C2") (pin "1") (pinfunction "1_1") (pintype "passive"))
    )
    (net (code "69") (name "Net-(PCM5102-DEMP)") (class "Default")
      (node (ref "PCM5102") (pin "10") (pinfunction "DEMP_10") (pintype "bidirectional"))
      (node (ref "S_R1") (pin "1") (pinfunction "1_1") (pintype "passive"))
    )
    (net (code "70") (name "Net-(PCM5102-LDOO)") (class "Default")
      (node (ref "PCM5102") (pin "18") (pinfunction "LDOO_18") (pintype "bidirectional"))
      (node (ref "S_C4") (pin "2") (pinfunction "2_2") (pintype "passive"))
    )
    (net (code "71") (name "Net-(PCM5102-OUTL)") (class "Default")
      (node (ref "C7") (pin "1") (pinfunction "1_1") (pintype "passive"))
      (node (ref "PCM5102") (pin "6") (pinfunction "OUTL_6") (pintype "bidirectional"))
      (node (ref "R9") (pin "1") (pinfunction "1_1") (pintype "passive"))
    )
    (net (code "72") (name "Net-(PCM5102-OUTR)") (class "Default")
      (node (ref "C6") (pin "1") (pinfunction "1_1") (pintype "passive"))
      (node (ref "PCM5102") (pin "7") (pinfunction "OUTR_7") (pintype "bidirectional"))
      (node (ref "R7") (pin "1") (pinfunction "1_1") (pintype "passive"))
    )
    (net (code "73") (name "Net-(PCM5102-VNEG)") (class "Default")
      (node (ref "PCM5102") (pin "5") (pinfunction "VNEG_5") (pintype "bidirectional"))
      (node (ref "S_C3") (pin "1") (pinfunction "1_1") (pintype "passive"))
    )
    (net (code "74") (name "Net-(PCM5102-XSMT)") (class "Default")
      (node (ref "PCM5102") (pin "17") (pinfunction "XSMT_17") (pintype "bidirectional"))
      (node (ref "S_R2") (pin "1") (pinfunction "1_1") (pintype "passive"))
    )
    (net (code "75") (name "Net-(PWR_UE-Pad3)") (class "Default")
      (node (ref "PWR_UE") (pin "3") (pinfunction "3_3") (pintype "passive"))
      (node (ref "SV4") (pin "8") (pinfunction "8_8") (pintype "passive"))
    )
    (net (code "76") (name "Net-(Q2-2)") (class "Default")
      (node (ref "C2") (pin "1") (pinfunction "1_1") (pintype "passive"))
      (node (ref "Q2") (pin "4") (pinfunction "2_4") (pintype "passive"))
      (node (ref "U$2") (pin "2") (pinfunction "PA01_2") (pintype "bidirectional"))
    )
    (net (code "77") (name "Net-(U$1-HOLD)") (class "Default")
      (node (ref "F_R14") (pin "1") (pinfunction "1_1") (pintype "passive"))
      (node (ref "U$1") (pin "3") (pinfunction "WP_3") (pintype "bidirectional"))
      (node (ref "U$1") (pin "7") (pinfunction "HOLD_7") (pintype "bidirectional"))
    )
    (net (code "78") (name "Net-(U$2-PA00)") (class "Default")
      (node (ref "C1") (pin "1") (pinfunction "1_1") (pintype "passive"))
      (node (ref "Q2") (pin "1") (pinfunction "1_1") (pintype "passive"))
      (node (ref "U$2") (pin "1") (pinfunction "PA00_1") (pintype "bidirectional"))
    )
    (net (code "79") (name "Net-(U$2-PA24)") (class "Default")
      (node (ref "U$2") (pin "23") (pinfunction "PA24_23") (pintype "bidirectional"))
      (node (ref "USB") (pin "2") (pinfunction "D-_2") (pintype "bidirectional"))
    )
    (net (code "80") (name "Net-(U$2-PA25)") (class "Default")
      (node (ref "U$2") (pin "24") (pinfunction "PA25_24") (pintype "bidirectional"))
      (node (ref "USB") (pin "3") (pinfunction "D+_3") (pintype "bidirectional"))
    )
    (net (code "81") (name "Net-(U$2-VDDCORE)") (class "Default")
      (node (ref "C8") (pin "1") (pinfunction "1_1") (pintype "passive"))
      (node (ref "U$2") (pin "29") (pinfunction "VDDCORE_29") (pintype "bidirectional"))
    )
    (net (code "82") (name "Net-(USB-VCC)") (class "Default")
      (node (ref "PWR_UE") (pin "1") (pinfunction "1_1") (pintype "passive"))
      (node (ref "USB") (pin "1") (pinfunction "VCC_1") (pintype "power_in"))
    )
    (net (code "83") (name "VCC") (class "Default")
      (node (ref "C22") (pin "+") (pinfunction "+_+") (pintype "passive"))
      (node (ref "C5") (pin "1") (pinfunction "1_1") (pintype "passive"))
      (node (ref "IC2") (pin "4") (pinfunction "OUT_4") (pintype "passive"))
      (node (ref "ICE40UP5K") (pin "29") (pinfunction "VCCPLL_29") (pintype "power_in"))
      (node (ref "ICE40UP5K") (pin "30") (pinfunction "VCC2_30") (pintype "power_in"))
      (node (ref "ICE40UP5K") (pin "5") (pinfunction "VCC_5") (pintype "power_in"))
    )
    (net (code "84") (name "unconnected-(D1-K1-Pad1)") (class "Default")
      (node (ref "D1") (pin "1") (pinfunction "K1_1") (pintype "passive"))
    )
    (net (code "85") (name "unconnected-(ICE40UP5KA-IOB_24A-Pad13)") (class "Default")
      (node (ref "ICE40UP5K") (pin "13") (pinfunction "IOB_24A_13") (pintype "bidirectional"))
    )
    (net (code "86") (name "unconnected-(ICE40UP5KA-IOT_41A-Pad28)") (class "Default")
      (node (ref "ICE40UP5K") (pin "28") (pinfunction "IOT_41A_28") (pintype "bidirectional"))
    )
    (net (code "87") (name "unconnected-(ICE40UP5KA-IOT_42B-Pad31)") (class "Default")
      (node (ref "ICE40UP5K") (pin "31") (pinfunction "IOT_42B_31") (pintype "bidirectional"))
    )
    (net (code "88") (name "unconnected-(ICE40UP5KA-IOT_43B-Pad32)") (class "Default")
      (node (ref "ICE40UP5K") (pin "32") (pinfunction "IOT_43B_32") (pintype "bidirectional"))
    )
    (net (code "89") (name "unconnected-(ICE40UP5KA-IOT_44B-Pad34)") (class "Default")
      (node (ref "ICE40UP5K") (pin "34") (pinfunction "IOT_44B_34") (pintype "bidirectional"))
    )
    (net (code "90") (name "unconnected-(ICE40UP5KA-IOT_46B-Pad35)") (class "Default")
      (node (ref "ICE40UP5K") (pin "35") (pinfunction "IOT_46B_35") (pintype "bidirectional"))
    )
    (net (code "91") (name "unconnected-(ICE40UP5KA-IOT_51A-Pad42)") (class "Default")
      (node (ref "ICE40UP5K") (pin "42") (pinfunction "IOT_51A_42") (pintype "bidirectional"))
    )
    (net (code "92") (name "unconnected-(U$2-PA08-Pad11)") (class "Default")
      (node (ref "U$2") (pin "11") (pinfunction "PA08_11") (pintype "bidirectional"))
    )
    (net (code "93") (name "unconnected-(U$2-PA09-Pad12)") (class "Default")
      (node (ref "U$2") (pin "12") (pinfunction "PA09_12") (pintype "bidirectional"))
    )
    (net (code "94") (name "unconnected-(U$2-PA10-Pad13)") (class "Default")
      (node (ref "U$2") (pin "13") (pinfunction "PA10_13") (pintype "bidirectional"))
    )
    (net (code "95") (name "unconnected-(U$2-PA11-Pad14)") (class "Default")
      (node (ref "U$2") (pin "14") (pinfunction "PA11_14") (pintype "bidirectional"))
    )
    (net (code "96") (name "unconnected-(U$2-PA14-Pad15)") (class "Default")
      (node (ref "U$2") (pin "15") (pinfunction "PA14_15") (pintype "bidirectional"))
    )
    (net (code "97") (name "unconnected-(U$2-PA15-Pad16)") (class "Default")
      (node (ref "U$2") (pin "16") (pinfunction "PA15_16") (pintype "bidirectional"))
    )
    (net (code "98") (name "unconnected-(U$2-PA27-Pad25)") (class "Default")
      (node (ref "U$2") (pin "25") (pinfunction "PA27_25") (pintype "bidirectional"))
    )
    (net (code "99") (name "unconnected-(U$2-PA28-Pad27)") (class "Default")
      (node (ref "U$2") (pin "27") (pinfunction "PA28_27") (pintype "bidirectional"))
    )
    (net (code "100") (name "unconnected-(USB-ID-Pad4)") (class "Default")
      (node (ref "USB") (pin "4") (pinfunction "ID_4") (pintype "bidirectional"))
    )
  )
)
